# attendance_SYS.net
KiCad netlist of a schematic drawn in Altium Designer
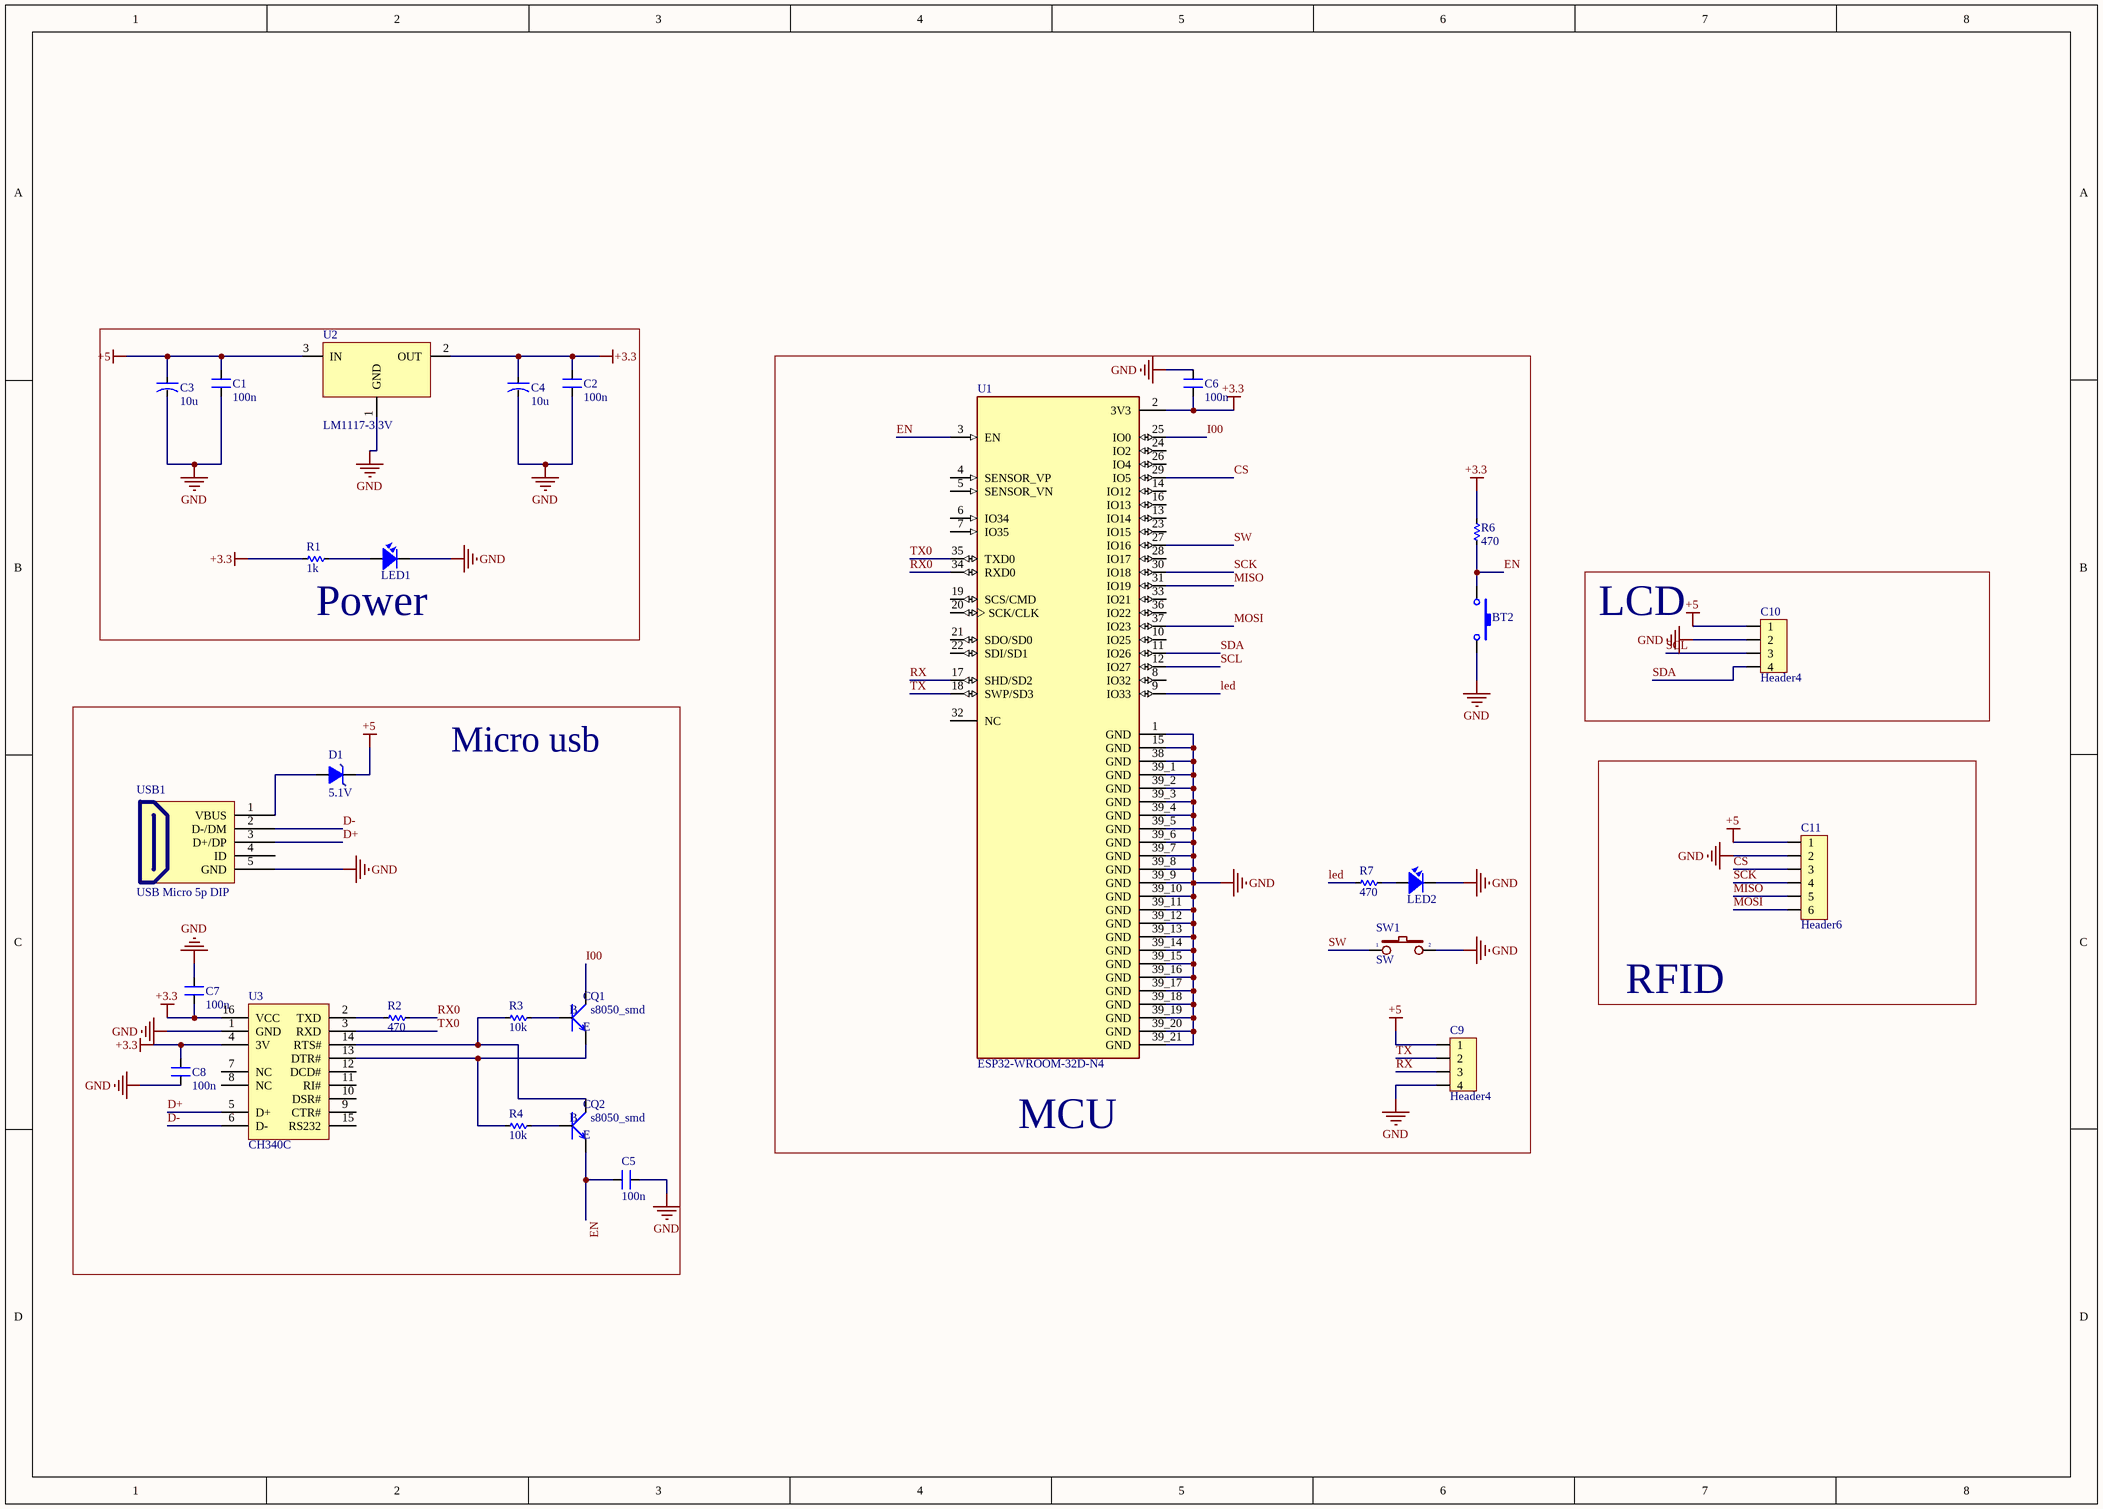
[diagram p0: attendance_SYS.SchDoc]

(export (version "E")
  (design (tool "Eeschema 10.0.6"))
  (components
    (comp (ref "BT2")
      (value "Nut Nhan 2 Chan SMD 3x6x2.5")
      (footprint "Nut Nhan 2 Chan SMD 3x6x2.5")
      (libsource (lib "Component") (part "Nut Nhan 2 Chan SMD 3x6x2.5"))
    )
    (comp (ref "C1") (value "100n") (footprint "CN-SMD-1206") (libsource (lib "Library") (part "CN")))
    (comp (ref "C2") (value "100n") (footprint "CN-SMD-1206") (libsource (lib "Library") (part "CN")))
    (comp (ref "C3")
      (value "10u")
      (footprint "CAP-ALU-SMD-5.5x5.5")
      (description "Polarized Capacitor (Axial)")
      (fields (field (name "PUBLISHER") "Altium Limited"))
      (libsource (lib "Library") (part "CN-SMD"))
    )
    (comp (ref "C4")
      (value "10u")
      (footprint "CAP-ALU-SMD-5.5x5.5")
      (description "Polarized Capacitor (Axial)")
      (fields (field (name "PUBLISHER") "Altium Limited"))
      (libsource (lib "Library") (part "CN-SMD"))
    )
    (comp (ref "C5") (value "100n") (footprint "CN-SMD-1206") (libsource (lib "Library") (part "CN")))
    (comp (ref "C6") (value "100n") (footprint "CN-SMD-1206") (libsource (lib "Library") (part "CN")))
    (comp (ref "C7") (value "100n") (footprint "CN-SMD-1206") (libsource (lib "Library") (part "CN")))
    (comp (ref "C8") (value "100n") (footprint "CN-SMD-1206") (libsource (lib "Library") (part "CN")))
    (comp (ref "C9")
      (value "Header4")
      (footprint "HDR4")
      (description "Header IDC, 4 x 1 Pin Vertical 2.54mm Pitch (Non-Boxed, Male)")
      (fields
        (field (name "MANUFACTURER") "Würth Elektronik eiSos GmbH")
        (field (name "PARTNO") "613002143121")
        (field (name "CREATED BY") "Karrer Zheng")
      )
      (libsource (lib "Library") (part "Header4"))
    )
    (comp (ref "C10")
      (value "Header4")
      (footprint "HDR4")
      (description "Header IDC, 4 x 1 Pin Vertical 2.54mm Pitch (Non-Boxed, Male)")
      (fields
        (field (name "MANUFACTURER") "Würth Elektronik eiSos GmbH")
        (field (name "PARTNO") "613002143121")
        (field (name "CREATED BY") "Karrer Zheng")
      )
      (libsource (lib "Library") (part "Header4"))
    )
    (comp (ref "C11")
      (value "Header6")
      (footprint "HDR6")
      (description "Header IDC, 6 x 1 Pin Vertical 2.54mm Pitch (Non-Boxed, Male)")
      (fields
        (field (name "MANUFACTURER") "Würth Elektronik eiSos GmbH")
        (field (name "PARTNO") "613002143121")
        (field (name "CREATED BY") "Karrer Zheng")
      )
      (libsource (lib "Library") (part "Header6"))
    )
    (comp (ref "D1")
      (value "5.1V")
      (footprint "DIODE ZENNER SMD SOD80")
      (description "Dán")
      (libsource (lib "Diode") (part "Diode Zener 5.1V"))
    )
    (comp (ref "LED1") (value "LED") (footprint "LED-1206-Red") (libsource (lib "Library") (part "LED SMD")))
    (comp (ref "LED2")
      (value "LED")
      (footprint "LED-5MM-GREEN")
      (description "LED Single colour Green and Red")
      (libsource (lib "Library") (part "LED"))
    )
    (comp (ref "Q1")
      (value "s8050_smd")
      (footprint "SOT-23")
      (description "Bipolar (BJT) Transistor NPN 25 V 500 mA 150MHz 300 mW Surface Mount SOT-23")
      (fields (field (name "MF") "UMW") (field (name "MP") "S8050"))
      (libsource (lib "Library") (part "s8050_smd"))
    )
    (comp (ref "Q2")
      (value "s8050_smd")
      (footprint "SOT-23")
      (description "Bipolar (BJT) Transistor NPN 25 V 500 mA 150MHz 300 mW Surface Mount SOT-23")
      (fields (field (name "MF") "UMW") (field (name "MP") "S8050"))
      (libsource (lib "Library") (part "s8050_smd"))
    )
    (comp (ref "R1")
      (value "1k")
      (footprint "RES-SMD-1206")
      (description "Resistor")
      (fields
        (field (name "MANUFACTURER") "Generic Components")
        (field (name "PUBLISHER") "Altium Hobart Technology Centre")
      )
      (libsource (lib "Library") (part "Res-SMD"))
    )
    (comp (ref "R2")
      (value "470")
      (footprint "RES-SMD-1206")
      (description "Resistor")
      (fields
        (field (name "MANUFACTURER") "Generic Components")
        (field (name "PUBLISHER") "Altium Hobart Technology Centre")
      )
      (libsource (lib "Library") (part "Res-SMD"))
    )
    (comp (ref "R3")
      (value "10k")
      (footprint "RES-SMD-1206")
      (description "Resistor")
      (fields
        (field (name "MANUFACTURER") "Generic Components")
        (field (name "PUBLISHER") "Altium Hobart Technology Centre")
      )
      (libsource (lib "Library") (part "Res-SMD"))
    )
    (comp (ref "R4")
      (value "10k")
      (footprint "RES-SMD-1206")
      (description "Resistor")
      (fields
        (field (name "MANUFACTURER") "Generic Components")
        (field (name "PUBLISHER") "Altium Hobart Technology Centre")
      )
      (libsource (lib "Library") (part "Res-SMD"))
    )
    (comp (ref "R6")
      (value "470")
      (footprint "RES-SMD-1206")
      (description "Resistor")
      (fields
        (field (name "MANUFACTURER") "Generic Components")
        (field (name "PUBLISHER") "Altium Hobart Technology Centre")
      )
      (libsource (lib "Library") (part "Res-SMD"))
    )
    (comp (ref "R7")
      (value "470")
      (footprint "RES-SMD-1206")
      (description "Resistor")
      (fields
        (field (name "MANUFACTURER") "Generic Components")
        (field (name "PUBLISHER") "Altium Hobart Technology Centre")
      )
      (libsource (lib "Library") (part "Res-SMD"))
    )
    (comp (ref "SW1")
      (value "SW")
      (footprint "SW1-DIP-12x12x8-Red")
      (description "Switch button 2 pin")
      (libsource (lib "Library") (part "SW2"))
    )
    (comp (ref "U1")
      (value "ESP32-WROOM-32D-N4")
      (footprint "MODULE_ESP32-WROOM-32D-N4")
      (fields (field (name "MF") "Espressif Systems"))
      (libsource (lib "biualtium") (part "ESP32-WROOM-32D-N4"))
    )
    (comp (ref "U2")
      (value "LM1117-3.3V")
      (footprint "SOT223")
      (description "800mA Low-Dropout Linear Regulator")
      (fields (field (name "CREATOR") "Nguyen Ba Bien"))
      (libsource (lib "Library") (part "LM1117"))
    )
    (comp (ref "U3")
      (value "CH340C")
      (footprint "SO16")
      (description "High and Low Side Driver")
      (fields (field (name "PUBLISHER") "Altium Limited"))
      (libsource (lib "Library") (part "CH340C"))
    )
    (comp (ref "USB1")
      (value "USB Micro 5p DIP")
      (footprint "USB Micro 5p DIP")
      (description "USB Type B")
      (libsource (lib "Component") (part "USB Micro 5p DIP"))
    )
  )
  (nets
    (net (code "1") (name "+3.3") (class "Default")
      (node (ref "C2") (pin "1") (pinfunction "1_1") (pintype "passive"))
      (node (ref "C4") (pin "1") (pinfunction "1_1") (pintype "passive"))
      (node (ref "C6") (pin "2") (pinfunction "2_2") (pintype "passive"))
      (node (ref "C7") (pin "2") (pinfunction "2_2") (pintype "passive"))
      (node (ref "C8") (pin "1") (pinfunction "1_1") (pintype "passive"))
      (node (ref "R1") (pin "2") (pinfunction "2_2") (pintype "passive"))
      (node (ref "R6") (pin "2") (pinfunction "2_2") (pintype "passive"))
      (node (ref "U1") (pin "2") (pinfunction "3V3_2") (pintype "power_in"))
      (node (ref "U2") (pin "2") (pinfunction "OUT_2") (pintype "passive"))
      (node (ref "U3") (pin "16") (pinfunction "VCC_16") (pintype "passive"))
      (node (ref "U3") (pin "4") (pinfunction "3V_4") (pintype "passive"))
    )
    (net (code "2") (name "+5") (class "Default")
      (node (ref "C1") (pin "1") (pinfunction "1_1") (pintype "passive"))
      (node (ref "C10") (pin "1") (pinfunction "1_1") (pintype "passive"))
      (node (ref "C11") (pin "1") (pinfunction "1_1") (pintype "passive"))
      (node (ref "C3") (pin "1") (pinfunction "1_1") (pintype "passive"))
      (node (ref "C9") (pin "1") (pinfunction "1_1") (pintype "passive"))
      (node (ref "D1") (pin "2") (pinfunction "K_2") (pintype "passive"))
      (node (ref "U2") (pin "3") (pinfunction "IN_3") (pintype "passive"))
    )
    (net (code "3") (name "/CS") (class "Default")
      (node (ref "C11") (pin "3") (pinfunction "3_3") (pintype "passive"))
      (node (ref "U1") (pin "29") (pinfunction "IO5_29") (pintype "bidirectional"))
    )
    (net (code "4") (name "/D+") (class "Default")
      (node (ref "U3") (pin "5") (pinfunction "D+_5") (pintype "passive"))
      (node (ref "USB1") (pin "3") (pinfunction "D+/DP_3") (pintype "passive"))
    )
    (net (code "5") (name "/D-") (class "Default")
      (node (ref "U3") (pin "6") (pinfunction "D-_6") (pintype "passive"))
      (node (ref "USB1") (pin "2") (pinfunction "D-/DM_2") (pintype "passive"))
    )
    (net (code "6") (name "/EN") (class "Default")
      (node (ref "BT2") (pin "1") (pinfunction "1_1") (pintype "passive"))
      (node (ref "C5") (pin "1") (pinfunction "1_1") (pintype "passive"))
      (node (ref "Q2") (pin "2") (pinfunction "E_2") (pintype "passive"))
      (node (ref "R6") (pin "1") (pinfunction "1_1") (pintype "passive"))
      (node (ref "U1") (pin "3") (pinfunction "EN_3") (pintype "input"))
    )
    (net (code "7") (name "/I00") (class "Default")
      (node (ref "Q1") (pin "3") (pinfunction "C_3") (pintype "passive"))
      (node (ref "U1") (pin "25") (pinfunction "IO0_25") (pintype "bidirectional"))
    )
    (net (code "8") (name "/MISO") (class "Default")
      (node (ref "C11") (pin "5") (pinfunction "5_5") (pintype "passive"))
      (node (ref "U1") (pin "31") (pinfunction "IO19_31") (pintype "bidirectional"))
    )
    (net (code "9") (name "/MOSI") (class "Default")
      (node (ref "C11") (pin "6") (pinfunction "6_6") (pintype "passive"))
      (node (ref "U1") (pin "37") (pinfunction "IO23_37") (pintype "bidirectional"))
    )
    (net (code "10") (name "/RX") (class "Default")
      (node (ref "C9") (pin "3") (pinfunction "3_3") (pintype "passive"))
      (node (ref "U1") (pin "17") (pinfunction "SHD/SD2_17") (pintype "bidirectional"))
    )
    (net (code "11") (name "/RX0") (class "Default")
      (node (ref "R2") (pin "1") (pinfunction "1_1") (pintype "passive"))
      (node (ref "U1") (pin "34") (pinfunction "RXD0_34") (pintype "bidirectional"))
    )
    (net (code "12") (name "/SCK") (class "Default")
      (node (ref "C11") (pin "4") (pinfunction "4_4") (pintype "passive"))
      (node (ref "U1") (pin "30") (pinfunction "IO18_30") (pintype "bidirectional"))
    )
    (net (code "13") (name "/SCL") (class "Default")
      (node (ref "C10") (pin "3") (pinfunction "3_3") (pintype "passive"))
      (node (ref "U1") (pin "12") (pinfunction "IO27_12") (pintype "bidirectional"))
    )
    (net (code "14") (name "/SDA") (class "Default")
      (node (ref "C10") (pin "4") (pinfunction "4_4") (pintype "passive"))
      (node (ref "U1") (pin "11") (pinfunction "IO26_11") (pintype "bidirectional"))
    )
    (net (code "15") (name "/SW") (class "Default")
      (node (ref "SW1") (pin "1") (pinfunction "1_1") (pintype "passive"))
      (node (ref "U1") (pin "27") (pinfunction "IO16_27") (pintype "bidirectional"))
    )
    (net (code "16") (name "/TX") (class "Default")
      (node (ref "C9") (pin "2") (pinfunction "2_2") (pintype "passive"))
      (node (ref "U1") (pin "18") (pinfunction "SWP/SD3_18") (pintype "bidirectional"))
    )
    (net (code "17") (name "/TX0") (class "Default")
      (node (ref "U1") (pin "35") (pinfunction "TXD0_35") (pintype "bidirectional"))
      (node (ref "U3") (pin "3") (pinfunction "RXD_3") (pintype "passive"))
    )
    (net (code "18") (name "/led") (class "Default")
      (node (ref "R7") (pin "2") (pinfunction "2_2") (pintype "passive"))
      (node (ref "U1") (pin "9") (pinfunction "IO33_9") (pintype "bidirectional"))
    )
    (net (code "19") (name "GND") (class "Default")
      (node (ref "BT2") (pin "2") (pinfunction "2_2") (pintype "passive"))
      (node (ref "C1") (pin "2") (pinfunction "2_2") (pintype "passive"))
      (node (ref "C10") (pin "2") (pinfunction "2_2") (pintype "passive"))
      (node (ref "C11") (pin "2") (pinfunction "2_2") (pintype "passive"))
      (node (ref "C2") (pin "2") (pinfunction "2_2") (pintype "passive"))
      (node (ref "C3") (pin "2") (pinfunction "2_2") (pintype "passive"))
      (node (ref "C4") (pin "2") (pinfunction "2_2") (pintype "passive"))
      (node (ref "C5") (pin "2") (pinfunction "2_2") (pintype "passive"))
      (node (ref "C6") (pin "1") (pinfunction "1_1") (pintype "passive"))
      (node (ref "C7") (pin "1") (pinfunction "1_1") (pintype "passive"))
      (node (ref "C8") (pin "2") (pinfunction "2_2") (pintype "passive"))
      (node (ref "C9") (pin "4") (pinfunction "4_4") (pintype "passive"))
      (node (ref "LED1") (pin "2") (pinfunction "2_2") (pintype "passive"))
      (node (ref "LED2") (pin "2") (pinfunction "2_2") (pintype "passive"))
      (node (ref "SW1") (pin "2") (pinfunction "2_2") (pintype "passive"))
      (node (ref "U1") (pin "1") (pinfunction "GND_1") (pintype "power_in"))
      (node (ref "U1") (pin "15") (pinfunction "GND_15") (pintype "power_in"))
      (node (ref "U1") (pin "38") (pinfunction "GND_38") (pintype "power_in"))
      (node (ref "U1") (pin "39_1") (pinfunction "GND_39_1") (pintype "power_in"))
      (node (ref "U1") (pin "39_10") (pinfunction "GND_39_10") (pintype "power_in"))
      (node (ref "U1") (pin "39_11") (pinfunction "GND_39_11") (pintype "power_in"))
      (node (ref "U1") (pin "39_12") (pinfunction "GND_39_12") (pintype "power_in"))
      (node (ref "U1") (pin "39_13") (pinfunction "GND_39_13") (pintype "power_in"))
      (node (ref "U1") (pin "39_14") (pinfunction "GND_39_14") (pintype "power_in"))
      (node (ref "U1") (pin "39_15") (pinfunction "GND_39_15") (pintype "power_in"))
      (node (ref "U1") (pin "39_16") (pinfunction "GND_39_16") (pintype "power_in"))
      (node (ref "U1") (pin "39_17") (pinfunction "GND_39_17") (pintype "power_in"))
      (node (ref "U1") (pin "39_18") (pinfunction "GND_39_18") (pintype "power_in"))
      (node (ref "U1") (pin "39_19") (pinfunction "GND_39_19") (pintype "power_in"))
      (node (ref "U1") (pin "39_2") (pinfunction "GND_39_2") (pintype "power_in"))
      (node (ref "U1") (pin "39_20") (pinfunction "GND_39_20") (pintype "power_in"))
      (node (ref "U1") (pin "39_21") (pinfunction "GND_39_21") (pintype "power_in"))
      (node (ref "U1") (pin "39_3") (pinfunction "GND_39_3") (pintype "power_in"))
      (node (ref "U1") (pin "39_4") (pinfunction "GND_39_4") (pintype "power_in"))
      (node (ref "U1") (pin "39_5") (pinfunction "GND_39_5") (pintype "power_in"))
      (node (ref "U1") (pin "39_6") (pinfunction "GND_39_6") (pintype "power_in"))
      (node (ref "U1") (pin "39_7") (pinfunction "GND_39_7") (pintype "power_in"))
      (node (ref "U1") (pin "39_8") (pinfunction "GND_39_8") (pintype "power_in"))
      (node (ref "U1") (pin "39_9") (pinfunction "GND_39_9") (pintype "power_in"))
      (node (ref "U2") (pin "1") (pinfunction "GND_1") (pintype "passive"))
      (node (ref "U3") (pin "1") (pinfunction "GND_1") (pintype "passive"))
      (node (ref "USB1") (pin "5") (pinfunction "GND_5") (pintype "passive"))
    )
    (net (code "20") (name "Net-(D1-A)") (class "Default")
      (node (ref "D1") (pin "1") (pinfunction "A_1") (pintype "passive"))
      (node (ref "USB1") (pin "1") (pinfunction "VBUS_1") (pintype "passive"))
    )
    (net (code "21") (name "Net-(LED1-Pad1)") (class "Default")
      (node (ref "LED1") (pin "1") (pinfunction "1_1") (pintype "passive"))
      (node (ref "R1") (pin "1") (pinfunction "1_1") (pintype "passive"))
    )
    (net (code "22") (name "Net-(LED2-Pad1)") (class "Default")
      (node (ref "LED2") (pin "1") (pinfunction "1_1") (pintype "passive"))
      (node (ref "R7") (pin "1") (pinfunction "1_1") (pintype "passive"))
    )
    (net (code "23") (name "Net-(Q1-B)") (class "Default")
      (node (ref "Q1") (pin "1") (pinfunction "B_1") (pintype "passive"))
      (node (ref "R3") (pin "1") (pinfunction "1_1") (pintype "passive"))
    )
    (net (code "24") (name "Net-(Q1-E)") (class "Default")
      (node (ref "Q1") (pin "2") (pinfunction "E_2") (pintype "passive"))
      (node (ref "R4") (pin "2") (pinfunction "2_2") (pintype "passive"))
      (node (ref "U3") (pin "13") (pinfunction "DTR#_13") (pintype "passive"))
    )
    (net (code "25") (name "Net-(Q2-B)") (class "Default")
      (node (ref "Q2") (pin "1") (pinfunction "B_1") (pintype "passive"))
      (node (ref "R4") (pin "1") (pinfunction "1_1") (pintype "passive"))
    )
    (net (code "26") (name "Net-(Q2-C)") (class "Default")
      (node (ref "Q2") (pin "3") (pinfunction "C_3") (pintype "passive"))
      (node (ref "R3") (pin "2") (pinfunction "2_2") (pintype "passive"))
      (node (ref "U3") (pin "14") (pinfunction "RTS#_14") (pintype "passive"))
    )
    (net (code "27") (name "Net-(U3-TXD)") (class "Default")
      (node (ref "R2") (pin "2") (pinfunction "2_2") (pintype "passive"))
      (node (ref "U3") (pin "2") (pinfunction "TXD_2") (pintype "passive"))
    )
    (net (code "28") (name "unconnected-(U1-IO2-Pad24)") (class "Default")
      (node (ref "U1") (pin "24") (pinfunction "IO2_24") (pintype "bidirectional"))
    )
    (net (code "29") (name "unconnected-(U1-IO4-Pad26)") (class "Default")
      (node (ref "U1") (pin "26") (pinfunction "IO4_26") (pintype "bidirectional"))
    )
    (net (code "30") (name "unconnected-(U1-IO12-Pad14)") (class "Default")
      (node (ref "U1") (pin "14") (pinfunction "IO12_14") (pintype "bidirectional"))
    )
    (net (code "31") (name "unconnected-(U1-IO13-Pad16)") (class "Default")
      (node (ref "U1") (pin "16") (pinfunction "IO13_16") (pintype "bidirectional"))
    )
    (net (code "32") (name "unconnected-(U1-IO14-Pad13)") (class "Default")
      (node (ref "U1") (pin "13") (pinfunction "IO14_13") (pintype "bidirectional"))
    )
    (net (code "33") (name "unconnected-(U1-IO15-Pad23)") (class "Default")
      (node (ref "U1") (pin "23") (pinfunction "IO15_23") (pintype "bidirectional"))
    )
    (net (code "34") (name "unconnected-(U1-IO17-Pad28)") (class "Default")
      (node (ref "U1") (pin "28") (pinfunction "IO17_28") (pintype "bidirectional"))
    )
    (net (code "35") (name "unconnected-(U1-IO21-Pad33)") (class "Default")
      (node (ref "U1") (pin "33") (pinfunction "IO21_33") (pintype "bidirectional"))
    )
    (net (code "36") (name "unconnected-(U1-IO22-Pad36)") (class "Default")
      (node (ref "U1") (pin "36") (pinfunction "IO22_36") (pintype "bidirectional"))
    )
    (net (code "37") (name "unconnected-(U1-IO25-Pad10)") (class "Default")
      (node (ref "U1") (pin "10") (pinfunction "IO25_10") (pintype "bidirectional"))
    )
    (net (code "38") (name "unconnected-(U1-IO32-Pad8)") (class "Default")
      (node (ref "U1") (pin "8") (pinfunction "IO32_8") (pintype "bidirectional"))
    )
    (net (code "39") (name "unconnected-(U1-IO34-Pad6)") (class "Default")
      (node (ref "U1") (pin "6") (pinfunction "IO34_6") (pintype "input"))
    )
    (net (code "40") (name "unconnected-(U1-IO35-Pad7)") (class "Default")
      (node (ref "U1") (pin "7") (pinfunction "IO35_7") (pintype "input"))
    )
    (net (code "41") (name "unconnected-(U1-NC-Pad32)") (class "Default")
      (node (ref "U1") (pin "32") (pinfunction "NC_32") (pintype "passive"))
    )
    (net (code "42") (name "unconnected-(U1-SCK{slash}CLK-Pad20)") (class "Default")
      (node (ref "U1") (pin "20") (pinfunction "SCK/CLK_20") (pintype "bidirectional"))
    )
    (net (code "43") (name "unconnected-(U1-SCS{slash}CMD-Pad19)") (class "Default")
      (node (ref "U1") (pin "19") (pinfunction "SCS/CMD_19") (pintype "bidirectional"))
    )
    (net (code "44") (name "unconnected-(U1-SDI{slash}SD1-Pad22)") (class "Default")
      (node (ref "U1") (pin "22") (pinfunction "SDI/SD1_22") (pintype "bidirectional"))
    )
    (net (code "45") (name "unconnected-(U1-SDO{slash}SD0-Pad21)") (class "Default")
      (node (ref "U1") (pin "21") (pinfunction "SDO/SD0_21") (pintype "bidirectional"))
    )
    (net (code "46") (name "unconnected-(U1-SENSOR_VN-Pad5)") (class "Default")
      (node (ref "U1") (pin "5") (pinfunction "SENSOR_VN_5") (pintype "input"))
    )
    (net (code "47") (name "unconnected-(U1-SENSOR_VP-Pad4)") (class "Default")
      (node (ref "U1") (pin "4") (pinfunction "SENSOR_VP_4") (pintype "input"))
    )
    (net (code "48") (name "unconnected-(U3-CTR#-Pad9)") (class "Default")
      (node (ref "U3") (pin "9") (pinfunction "CTR#_9") (pintype "passive"))
    )
    (net (code "49") (name "unconnected-(U3-DCD#-Pad12)") (class "Default")
      (node (ref "U3") (pin "12") (pinfunction "DCD#_12") (pintype "passive"))
    )
    (net (code "50") (name "unconnected-(U3-DSR#-Pad10)") (class "Default")
      (node (ref "U3") (pin "10") (pinfunction "DSR#_10") (pintype "passive"))
    )
    (net (code "51") (name "unconnected-(U3-NC-Pad7)") (class "Default")
      (node (ref "U3") (pin "7") (pinfunction "NC_7") (pintype "passive"))
    )
    (net (code "52") (name "unconnected-(U3-NC-Pad8)") (class "Default")
      (node (ref "U3") (pin "8") (pinfunction "NC_8") (pintype "passive"))
    )
    (net (code "53") (name "unconnected-(U3-RI#-Pad11)") (class "Default")
      (node (ref "U3") (pin "11") (pinfunction "RI#_11") (pintype "passive"))
    )
    (net (code "54") (name "unconnected-(U3-RS232-Pad15)") (class "Default")
      (node (ref "U3") (pin "15") (pinfunction "RS232_15") (pintype "passive"))
    )
    (net (code "55") (name "unconnected-(USB1-ID-Pad4)") (class "Default")
      (node (ref "USB1") (pin "4") (pinfunction "ID_4") (pintype "passive"))
    )
  )
)
